# MusicReactiveLEDStrip-V2.net
KiCad netlist of a schematic drawn in EAGLE
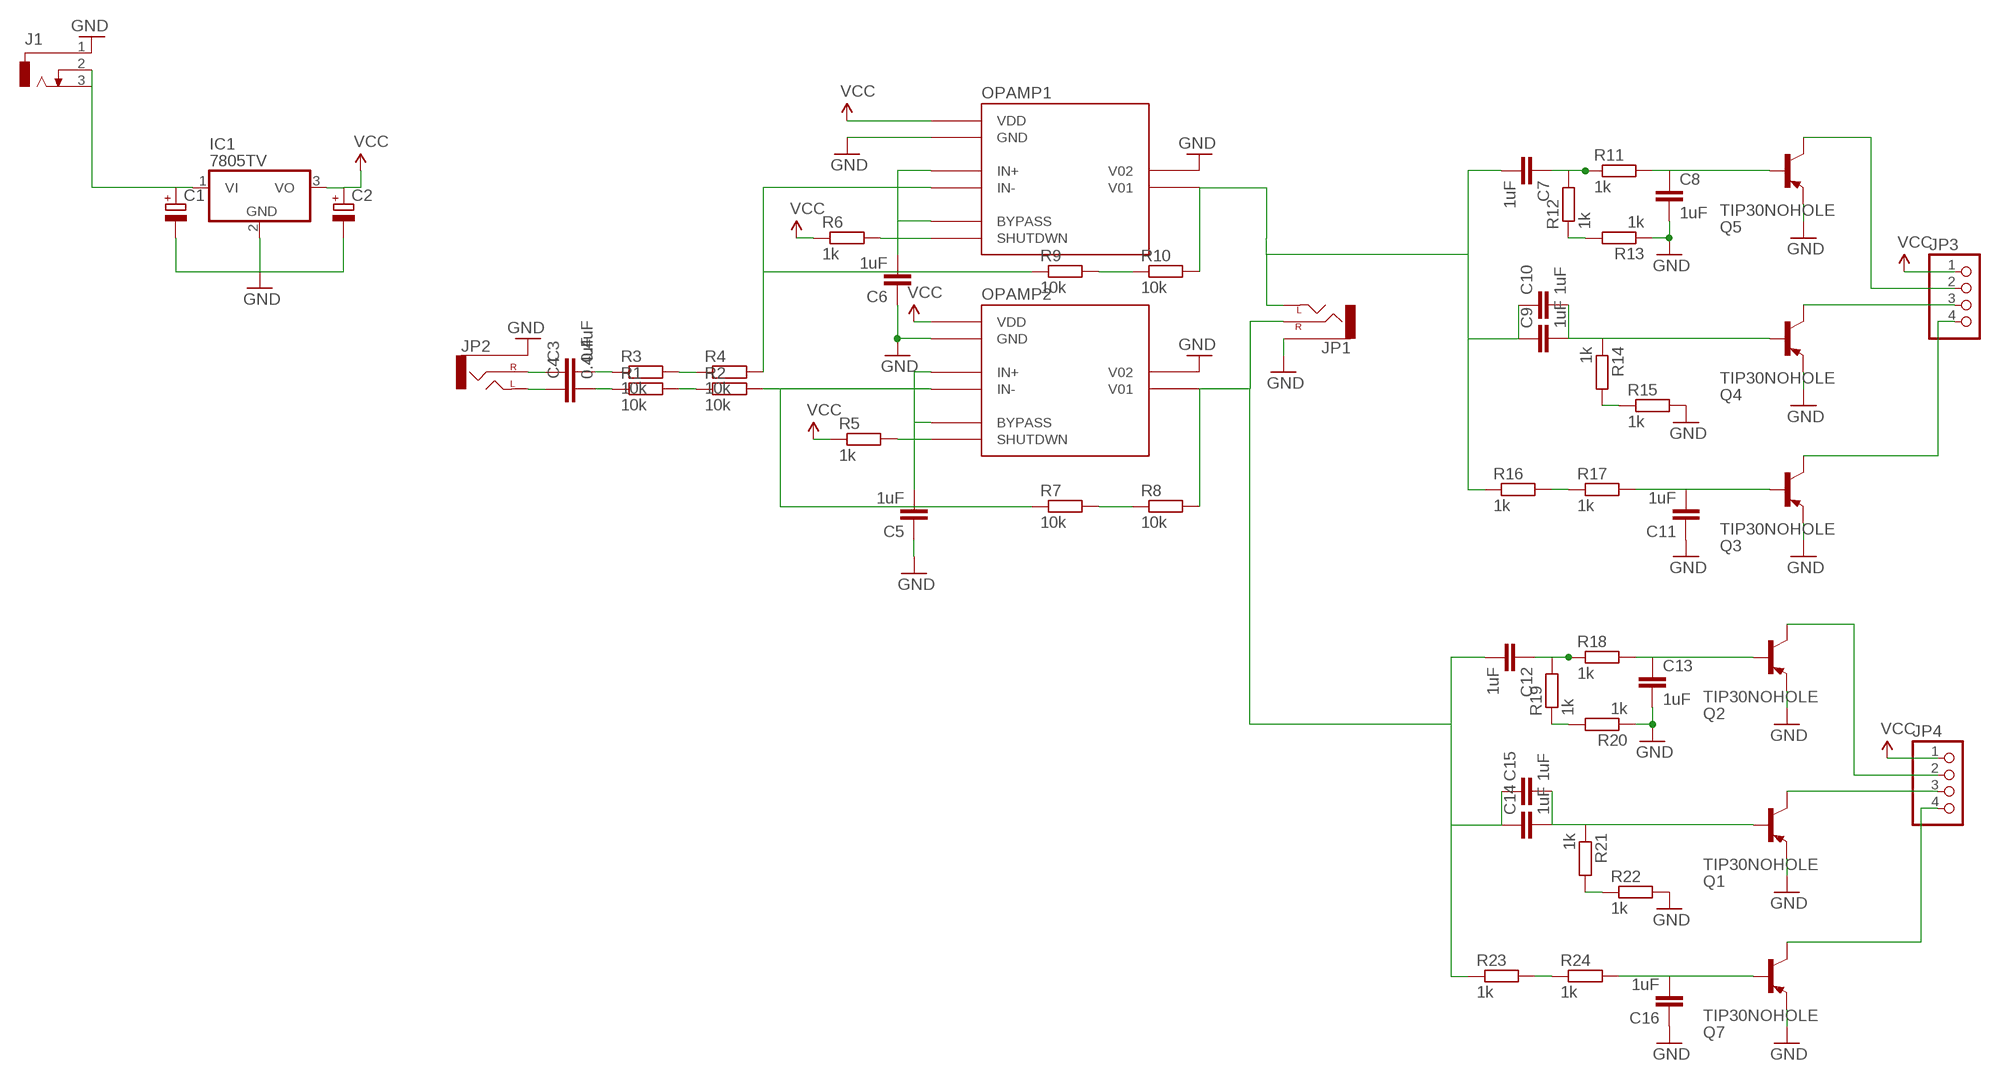
[diagram p0: schematic, sheet 1]

(export (version "E")
  (design (tool "Eeschema 10.0.6"))
  (components
    (comp (ref "C1")
      (value "CPOL-EUE2.5-6")
      (footprint "eagle-import:E2,5-6")
      (libsource (lib "eagle-import") (part "CPOL-EUE2.5-6"))
    )
    (comp (ref "C2")
      (value "CPOL-EUE2.5-6")
      (footprint "eagle-import:E2,5-6")
      (libsource (lib "eagle-import") (part "CPOL-EUE2.5-6"))
    )
    (comp (ref "C3")
      (value "0.4uF")
      (footprint "eagle-import:C050-025X075")
      (libsource (lib "eagle-import") (part "C-EU050-025X075"))
    )
    (comp (ref "C4")
      (value "0.4uF")
      (footprint "eagle-import:C050-025X075")
      (libsource (lib "eagle-import") (part "C-EU050-025X075"))
    )
    (comp (ref "C5")
      (value "1uF")
      (footprint "eagle-import:C050-025X075")
      (libsource (lib "eagle-import") (part "C-EU050-025X075"))
    )
    (comp (ref "C6")
      (value "1uF")
      (footprint "eagle-import:C050-025X075")
      (libsource (lib "eagle-import") (part "C-EU050-025X075"))
    )
    (comp (ref "C7")
      (value "1uF")
      (footprint "eagle-import:C050-025X075")
      (libsource (lib "eagle-import") (part "C-EU050-025X075"))
    )
    (comp (ref "C8")
      (value "1uF")
      (footprint "eagle-import:C050-025X075")
      (libsource (lib "eagle-import") (part "C-EU050-025X075"))
    )
    (comp (ref "C9")
      (value "1uF")
      (footprint "eagle-import:C050-025X075")
      (libsource (lib "eagle-import") (part "C-EU050-025X075"))
    )
    (comp (ref "C10")
      (value "1uF")
      (footprint "eagle-import:C050-025X075")
      (libsource (lib "eagle-import") (part "C-EU050-025X075"))
    )
    (comp (ref "C11")
      (value "1uF")
      (footprint "eagle-import:C050-025X075")
      (libsource (lib "eagle-import") (part "C-EU050-025X075"))
    )
    (comp (ref "C12")
      (value "1uF")
      (footprint "eagle-import:C050-025X075")
      (libsource (lib "eagle-import") (part "C-EU050-025X075"))
    )
    (comp (ref "C13")
      (value "1uF")
      (footprint "eagle-import:C050-025X075")
      (libsource (lib "eagle-import") (part "C-EU050-025X075"))
    )
    (comp (ref "C14")
      (value "1uF")
      (footprint "eagle-import:C050-025X075")
      (libsource (lib "eagle-import") (part "C-EU050-025X075"))
    )
    (comp (ref "C15")
      (value "1uF")
      (footprint "eagle-import:C050-025X075")
      (libsource (lib "eagle-import") (part "C-EU050-025X075"))
    )
    (comp (ref "C16")
      (value "1uF")
      (footprint "eagle-import:C050-025X075")
      (libsource (lib "eagle-import") (part "C-EU050-025X075"))
    )
    (comp (ref "IC1")
      (value "7805TV")
      (footprint "eagle-import:TO220V")
      (libsource (lib "eagle-import") (part "78TV05"))
    )
    (comp (ref "J1")
      (value "DCJ0303")
      (footprint "eagle-import:DCJ0303")
      (libsource (lib "eagle-import") (part "DCJ0303"))
    )
    (comp (ref "JP1")
      (value "AUDIO-JACKPTH")
      (footprint "eagle-import:AUDIO-JACK")
      (libsource (lib "eagle-import") (part "AUDIO-JACKPTH"))
    )
    (comp (ref "JP2")
      (value "AUDIO-JACKPTH")
      (footprint "eagle-import:AUDIO-JACK")
      (libsource (lib "eagle-import") (part "AUDIO-JACKPTH"))
    )
    (comp (ref "JP3")
      (value "PINHD-1X4")
      (footprint "eagle-import:1X04")
      (libsource (lib "eagle-import") (part "PINHD-1X4"))
    )
    (comp (ref "JP4")
      (value "PINHD-1X4")
      (footprint "eagle-import:1X04")
      (libsource (lib "eagle-import") (part "PINHD-1X4"))
    )
    (comp (ref "OPAMP1")
      (value "LM4871")
      (footprint "eagle-import:SO08")
      (libsource (lib "eagle-import") (part "LM4871"))
    )
    (comp (ref "OPAMP2")
      (value "LM4871")
      (footprint "eagle-import:SO08")
      (libsource (lib "eagle-import") (part "LM4871"))
    )
    (comp (ref "Q1")
      (value "TIP30NOHOLE")
      (footprint "eagle-import:TO220-NOHOLE")
      (libsource (lib "eagle-import") (part "TIP30NOHOLE"))
    )
    (comp (ref "Q2")
      (value "TIP30NOHOLE")
      (footprint "eagle-import:TO220-NOHOLE")
      (libsource (lib "eagle-import") (part "TIP30NOHOLE"))
    )
    (comp (ref "Q3")
      (value "TIP30NOHOLE")
      (footprint "eagle-import:TO220-NOHOLE")
      (libsource (lib "eagle-import") (part "TIP30NOHOLE"))
    )
    (comp (ref "Q4")
      (value "TIP30NOHOLE")
      (footprint "eagle-import:TO220-NOHOLE")
      (libsource (lib "eagle-import") (part "TIP30NOHOLE"))
    )
    (comp (ref "Q5")
      (value "TIP30NOHOLE")
      (footprint "eagle-import:TO220-NOHOLE")
      (libsource (lib "eagle-import") (part "TIP30NOHOLE"))
    )
    (comp (ref "Q7")
      (value "TIP30NOHOLE")
      (footprint "eagle-import:TO220-NOHOLE")
      (libsource (lib "eagle-import") (part "TIP30NOHOLE"))
    )
    (comp (ref "R1")
      (value "10k")
      (footprint "eagle-import:0207_10")
      (libsource (lib "eagle-import") (part "R-EU_0207/10"))
    )
    (comp (ref "R2")
      (value "10k")
      (footprint "eagle-import:0207_10")
      (libsource (lib "eagle-import") (part "R-EU_0207/10"))
    )
    (comp (ref "R3")
      (value "10k")
      (footprint "eagle-import:0207_10")
      (libsource (lib "eagle-import") (part "R-EU_0207/10"))
    )
    (comp (ref "R4")
      (value "10k")
      (footprint "eagle-import:0207_10")
      (libsource (lib "eagle-import") (part "R-EU_0207/10"))
    )
    (comp (ref "R5")
      (value "1k")
      (footprint "eagle-import:0207_10")
      (libsource (lib "eagle-import") (part "R-EU_0207/10"))
    )
    (comp (ref "R6")
      (value "1k")
      (footprint "eagle-import:0207_10")
      (libsource (lib "eagle-import") (part "R-EU_0207/10"))
    )
    (comp (ref "R7")
      (value "10k")
      (footprint "eagle-import:0207_10")
      (libsource (lib "eagle-import") (part "R-EU_0207/10"))
    )
    (comp (ref "R8")
      (value "10k")
      (footprint "eagle-import:0207_10")
      (libsource (lib "eagle-import") (part "R-EU_0207/10"))
    )
    (comp (ref "R9")
      (value "10k")
      (footprint "eagle-import:0207_10")
      (libsource (lib "eagle-import") (part "R-EU_0207/10"))
    )
    (comp (ref "R10")
      (value "10k")
      (footprint "eagle-import:0207_10")
      (libsource (lib "eagle-import") (part "R-EU_0207/10"))
    )
    (comp (ref "R11")
      (value "1k")
      (footprint "eagle-import:0207_10")
      (libsource (lib "eagle-import") (part "R-EU_0207/10"))
    )
    (comp (ref "R12")
      (value "1k")
      (footprint "eagle-import:0207_10")
      (libsource (lib "eagle-import") (part "R-EU_0207/10"))
    )
    (comp (ref "R13")
      (value "1k")
      (footprint "eagle-import:0207_10")
      (libsource (lib "eagle-import") (part "R-EU_0207/10"))
    )
    (comp (ref "R14")
      (value "1k")
      (footprint "eagle-import:0207_10")
      (libsource (lib "eagle-import") (part "R-EU_0207/10"))
    )
    (comp (ref "R15")
      (value "1k")
      (footprint "eagle-import:0207_10")
      (libsource (lib "eagle-import") (part "R-EU_0207/10"))
    )
    (comp (ref "R16")
      (value "1k")
      (footprint "eagle-import:0207_10")
      (libsource (lib "eagle-import") (part "R-EU_0207/10"))
    )
    (comp (ref "R17")
      (value "1k")
      (footprint "eagle-import:0207_10")
      (libsource (lib "eagle-import") (part "R-EU_0207/10"))
    )
    (comp (ref "R18")
      (value "1k")
      (footprint "eagle-import:0207_10")
      (libsource (lib "eagle-import") (part "R-EU_0207/10"))
    )
    (comp (ref "R19")
      (value "1k")
      (footprint "eagle-import:0207_10")
      (libsource (lib "eagle-import") (part "R-EU_0207/10"))
    )
    (comp (ref "R20")
      (value "1k")
      (footprint "eagle-import:0207_10")
      (libsource (lib "eagle-import") (part "R-EU_0207/10"))
    )
    (comp (ref "R21")
      (value "1k")
      (footprint "eagle-import:0207_10")
      (libsource (lib "eagle-import") (part "R-EU_0207/10"))
    )
    (comp (ref "R22")
      (value "1k")
      (footprint "eagle-import:0207_10")
      (libsource (lib "eagle-import") (part "R-EU_0207/10"))
    )
    (comp (ref "R23")
      (value "1k")
      (footprint "eagle-import:0207_10")
      (libsource (lib "eagle-import") (part "R-EU_0207/10"))
    )
    (comp (ref "R24")
      (value "1k")
      (footprint "eagle-import:0207_10")
      (libsource (lib "eagle-import") (part "R-EU_0207/10"))
    )
  )
  (nets
    (net (code "1") (name "GND") (class "Default")
      (node (ref "C1") (pin "-") (pinfunction "-_-") (pintype "passive"))
      (node (ref "C11") (pin "1") (pinfunction "1_1") (pintype "passive"))
      (node (ref "C13") (pin "2") (pinfunction "2_2") (pintype "passive"))
      (node (ref "C16") (pin "1") (pinfunction "1_1") (pintype "passive"))
      (node (ref "C2") (pin "-") (pinfunction "-_-") (pintype "passive"))
      (node (ref "C5") (pin "1") (pinfunction "1_1") (pintype "passive"))
      (node (ref "C6") (pin "1") (pinfunction "1_1") (pintype "passive"))
      (node (ref "C8") (pin "2") (pinfunction "2_2") (pintype "passive"))
      (node (ref "IC1") (pin "2") (pinfunction "GND_2") (pintype "passive"))
      (node (ref "J1") (pin "1") (pinfunction "1_1") (pintype "passive"))
      (node (ref "JP1") (pin "SLEEVE") (pinfunction "SLEEVE_SLEEVE") (pintype "bidirectional"))
      (node (ref "JP2") (pin "SLEEVE") (pinfunction "SLEEVE_SLEEVE") (pintype "bidirectional"))
      (node (ref "OPAMP1") (pin "7") (pinfunction "GND_7") (pintype "bidirectional"))
      (node (ref "OPAMP1") (pin "8") (pinfunction "V02_8") (pintype "bidirectional"))
      (node (ref "OPAMP2") (pin "7") (pinfunction "GND_7") (pintype "bidirectional"))
      (node (ref "OPAMP2") (pin "8") (pinfunction "V02_8") (pintype "bidirectional"))
      (node (ref "Q1") (pin "3") (pinfunction "E_3") (pintype "passive"))
      (node (ref "Q2") (pin "3") (pinfunction "E_3") (pintype "passive"))
      (node (ref "Q3") (pin "3") (pinfunction "E_3") (pintype "passive"))
      (node (ref "Q4") (pin "3") (pinfunction "E_3") (pintype "passive"))
      (node (ref "Q5") (pin "3") (pinfunction "E_3") (pintype "passive"))
      (node (ref "Q7") (pin "3") (pinfunction "E_3") (pintype "passive"))
      (node (ref "R13") (pin "1") (pinfunction "1_1") (pintype "passive"))
      (node (ref "R15") (pin "2") (pinfunction "2_2") (pintype "passive"))
      (node (ref "R20") (pin "1") (pinfunction "1_1") (pintype "passive"))
      (node (ref "R22") (pin "2") (pinfunction "2_2") (pintype "passive"))
    )
    (net (code "2") (name "Net-(C3-Pad2)") (class "Default")
      (node (ref "C3") (pin "2") (pinfunction "2_2") (pintype "passive"))
      (node (ref "R3") (pin "1") (pinfunction "1_1") (pintype "passive"))
    )
    (net (code "3") (name "Net-(C4-Pad2)") (class "Default")
      (node (ref "C4") (pin "2") (pinfunction "2_2") (pintype "passive"))
      (node (ref "R1") (pin "1") (pinfunction "1_1") (pintype "passive"))
    )
    (net (code "4") (name "Net-(C7-Pad1)") (class "Default")
      (node (ref "C7") (pin "1") (pinfunction "1_1") (pintype "passive"))
      (node (ref "R11") (pin "1") (pinfunction "1_1") (pintype "passive"))
      (node (ref "R12") (pin "2") (pinfunction "2_2") (pintype "passive"))
    )
    (net (code "5") (name "Net-(C12-Pad1)") (class "Default")
      (node (ref "C12") (pin "1") (pinfunction "1_1") (pintype "passive"))
      (node (ref "R18") (pin "1") (pinfunction "1_1") (pintype "passive"))
      (node (ref "R19") (pin "2") (pinfunction "2_2") (pintype "passive"))
    )
    (net (code "6") (name "Net-(IC1-VI)") (class "Default")
      (node (ref "C1") (pin "+") (pinfunction "+_+") (pintype "passive"))
      (node (ref "IC1") (pin "1") (pinfunction "VI_1") (pintype "input"))
      (node (ref "J1") (pin "2") (pinfunction "2_2") (pintype "passive"))
      (node (ref "J1") (pin "3") (pinfunction "3_3") (pintype "passive"))
    )
    (net (code "7") (name "Net-(JP1-LEFT)") (class "Default")
      (node (ref "C10") (pin "1") (pinfunction "1_1") (pintype "passive"))
      (node (ref "C7") (pin "2") (pinfunction "2_2") (pintype "passive"))
      (node (ref "C9") (pin "1") (pinfunction "1_1") (pintype "passive"))
      (node (ref "JP1") (pin "TIP") (pinfunction "LEFT_TIP") (pintype "bidirectional"))
      (node (ref "OPAMP1") (pin "5") (pinfunction "V01_5") (pintype "bidirectional"))
      (node (ref "R10") (pin "2") (pinfunction "2_2") (pintype "passive"))
      (node (ref "R16") (pin "1") (pinfunction "1_1") (pintype "passive"))
    )
    (net (code "8") (name "Net-(JP1-RIGHT)") (class "Default")
      (node (ref "C12") (pin "2") (pinfunction "2_2") (pintype "passive"))
      (node (ref "C14") (pin "1") (pinfunction "1_1") (pintype "passive"))
      (node (ref "C15") (pin "1") (pinfunction "1_1") (pintype "passive"))
      (node (ref "JP1") (pin "RING") (pinfunction "RIGHT_RING") (pintype "bidirectional"))
      (node (ref "OPAMP2") (pin "5") (pinfunction "V01_5") (pintype "bidirectional"))
      (node (ref "R23") (pin "1") (pinfunction "1_1") (pintype "passive"))
      (node (ref "R8") (pin "2") (pinfunction "2_2") (pintype "passive"))
    )
    (net (code "9") (name "Net-(JP2-LEFT)") (class "Default")
      (node (ref "C4") (pin "1") (pinfunction "1_1") (pintype "passive"))
      (node (ref "JP2") (pin "TIP") (pinfunction "LEFT_TIP") (pintype "bidirectional"))
    )
    (net (code "10") (name "Net-(JP2-RIGHT)") (class "Default")
      (node (ref "C3") (pin "1") (pinfunction "1_1") (pintype "passive"))
      (node (ref "JP2") (pin "RING") (pinfunction "RIGHT_RING") (pintype "bidirectional"))
    )
    (net (code "11") (name "Net-(OPAMP1-BYPASS)") (class "Default")
      (node (ref "C6") (pin "2") (pinfunction "2_2") (pintype "passive"))
      (node (ref "OPAMP1") (pin "2") (pinfunction "BYPASS_2") (pintype "bidirectional"))
      (node (ref "OPAMP1") (pin "3") (pinfunction "IN+_3") (pintype "bidirectional"))
    )
    (net (code "12") (name "Net-(OPAMP1-IN-)") (class "Default")
      (node (ref "OPAMP1") (pin "4") (pinfunction "IN-_4") (pintype "bidirectional"))
      (node (ref "R4") (pin "2") (pinfunction "2_2") (pintype "passive"))
      (node (ref "R9") (pin "1") (pinfunction "1_1") (pintype "passive"))
    )
    (net (code "13") (name "Net-(OPAMP1-SHUTDWN)") (class "Default")
      (node (ref "OPAMP1") (pin "1") (pinfunction "SHUTDWN_1") (pintype "bidirectional"))
      (node (ref "R6") (pin "2") (pinfunction "2_2") (pintype "passive"))
    )
    (net (code "14") (name "Net-(OPAMP2-BYPASS)") (class "Default")
      (node (ref "C5") (pin "2") (pinfunction "2_2") (pintype "passive"))
      (node (ref "OPAMP2") (pin "2") (pinfunction "BYPASS_2") (pintype "bidirectional"))
      (node (ref "OPAMP2") (pin "3") (pinfunction "IN+_3") (pintype "bidirectional"))
    )
    (net (code "15") (name "Net-(OPAMP2-IN-)") (class "Default")
      (node (ref "OPAMP2") (pin "4") (pinfunction "IN-_4") (pintype "bidirectional"))
      (node (ref "R2") (pin "2") (pinfunction "2_2") (pintype "passive"))
      (node (ref "R7") (pin "1") (pinfunction "1_1") (pintype "passive"))
    )
    (net (code "16") (name "Net-(OPAMP2-SHUTDWN)") (class "Default")
      (node (ref "OPAMP2") (pin "1") (pinfunction "SHUTDWN_1") (pintype "bidirectional"))
      (node (ref "R5") (pin "2") (pinfunction "2_2") (pintype "passive"))
    )
    (net (code "17") (name "Net-(Q1-B)") (class "Default")
      (node (ref "C14") (pin "2") (pinfunction "2_2") (pintype "passive"))
      (node (ref "C15") (pin "2") (pinfunction "2_2") (pintype "passive"))
      (node (ref "Q1") (pin "1") (pinfunction "B_1") (pintype "passive"))
      (node (ref "R21") (pin "1") (pinfunction "1_1") (pintype "passive"))
    )
    (net (code "18") (name "Net-(Q1-C)") (class "Default")
      (node (ref "JP4") (pin "3") (pinfunction "3_3") (pintype "passive"))
      (node (ref "Q1") (pin "2") (pinfunction "C_2") (pintype "passive"))
    )
    (net (code "19") (name "Net-(Q2-B)") (class "Default")
      (node (ref "C13") (pin "1") (pinfunction "1_1") (pintype "passive"))
      (node (ref "Q2") (pin "1") (pinfunction "B_1") (pintype "passive"))
      (node (ref "R18") (pin "2") (pinfunction "2_2") (pintype "passive"))
    )
    (net (code "20") (name "Net-(Q2-C)") (class "Default")
      (node (ref "JP4") (pin "2") (pinfunction "2_2") (pintype "passive"))
      (node (ref "Q2") (pin "2") (pinfunction "C_2") (pintype "passive"))
    )
    (net (code "21") (name "Net-(Q3-B)") (class "Default")
      (node (ref "C11") (pin "2") (pinfunction "2_2") (pintype "passive"))
      (node (ref "Q3") (pin "1") (pinfunction "B_1") (pintype "passive"))
      (node (ref "R17") (pin "2") (pinfunction "2_2") (pintype "passive"))
    )
    (net (code "22") (name "Net-(Q3-C)") (class "Default")
      (node (ref "JP3") (pin "4") (pinfunction "4_4") (pintype "passive"))
      (node (ref "Q3") (pin "2") (pinfunction "C_2") (pintype "passive"))
    )
    (net (code "23") (name "Net-(Q4-B)") (class "Default")
      (node (ref "C10") (pin "2") (pinfunction "2_2") (pintype "passive"))
      (node (ref "C9") (pin "2") (pinfunction "2_2") (pintype "passive"))
      (node (ref "Q4") (pin "1") (pinfunction "B_1") (pintype "passive"))
      (node (ref "R14") (pin "1") (pinfunction "1_1") (pintype "passive"))
    )
    (net (code "24") (name "Net-(Q4-C)") (class "Default")
      (node (ref "JP3") (pin "3") (pinfunction "3_3") (pintype "passive"))
      (node (ref "Q4") (pin "2") (pinfunction "C_2") (pintype "passive"))
    )
    (net (code "25") (name "Net-(Q5-B)") (class "Default")
      (node (ref "C8") (pin "1") (pinfunction "1_1") (pintype "passive"))
      (node (ref "Q5") (pin "1") (pinfunction "B_1") (pintype "passive"))
      (node (ref "R11") (pin "2") (pinfunction "2_2") (pintype "passive"))
    )
    (net (code "26") (name "Net-(Q5-C)") (class "Default")
      (node (ref "JP3") (pin "2") (pinfunction "2_2") (pintype "passive"))
      (node (ref "Q5") (pin "2") (pinfunction "C_2") (pintype "passive"))
    )
    (net (code "27") (name "Net-(Q7-B)") (class "Default")
      (node (ref "C16") (pin "2") (pinfunction "2_2") (pintype "passive"))
      (node (ref "Q7") (pin "1") (pinfunction "B_1") (pintype "passive"))
      (node (ref "R24") (pin "2") (pinfunction "2_2") (pintype "passive"))
    )
    (net (code "28") (name "Net-(Q7-C)") (class "Default")
      (node (ref "JP4") (pin "4") (pinfunction "4_4") (pintype "passive"))
      (node (ref "Q7") (pin "2") (pinfunction "C_2") (pintype "passive"))
    )
    (net (code "29") (name "Net-(R1-Pad2)") (class "Default")
      (node (ref "R1") (pin "2") (pinfunction "2_2") (pintype "passive"))
      (node (ref "R2") (pin "1") (pinfunction "1_1") (pintype "passive"))
    )
    (net (code "30") (name "Net-(R3-Pad2)") (class "Default")
      (node (ref "R3") (pin "2") (pinfunction "2_2") (pintype "passive"))
      (node (ref "R4") (pin "1") (pinfunction "1_1") (pintype "passive"))
    )
    (net (code "31") (name "Net-(R7-Pad2)") (class "Default")
      (node (ref "R7") (pin "2") (pinfunction "2_2") (pintype "passive"))
      (node (ref "R8") (pin "1") (pinfunction "1_1") (pintype "passive"))
    )
    (net (code "32") (name "Net-(R10-Pad1)") (class "Default")
      (node (ref "R10") (pin "1") (pinfunction "1_1") (pintype "passive"))
      (node (ref "R9") (pin "2") (pinfunction "2_2") (pintype "passive"))
    )
    (net (code "33") (name "Net-(R12-Pad1)") (class "Default")
      (node (ref "R12") (pin "1") (pinfunction "1_1") (pintype "passive"))
      (node (ref "R13") (pin "2") (pinfunction "2_2") (pintype "passive"))
    )
    (net (code "34") (name "Net-(R14-Pad2)") (class "Default")
      (node (ref "R14") (pin "2") (pinfunction "2_2") (pintype "passive"))
      (node (ref "R15") (pin "1") (pinfunction "1_1") (pintype "passive"))
    )
    (net (code "35") (name "Net-(R16-Pad2)") (class "Default")
      (node (ref "R16") (pin "2") (pinfunction "2_2") (pintype "passive"))
      (node (ref "R17") (pin "1") (pinfunction "1_1") (pintype "passive"))
    )
    (net (code "36") (name "Net-(R19-Pad1)") (class "Default")
      (node (ref "R19") (pin "1") (pinfunction "1_1") (pintype "passive"))
      (node (ref "R20") (pin "2") (pinfunction "2_2") (pintype "passive"))
    )
    (net (code "37") (name "Net-(R21-Pad2)") (class "Default")
      (node (ref "R21") (pin "2") (pinfunction "2_2") (pintype "passive"))
      (node (ref "R22") (pin "1") (pinfunction "1_1") (pintype "passive"))
    )
    (net (code "38") (name "Net-(R23-Pad2)") (class "Default")
      (node (ref "R23") (pin "2") (pinfunction "2_2") (pintype "passive"))
      (node (ref "R24") (pin "1") (pinfunction "1_1") (pintype "passive"))
    )
    (net (code "39") (name "VCC") (class "Default")
      (node (ref "C2") (pin "+") (pinfunction "+_+") (pintype "passive"))
      (node (ref "IC1") (pin "3") (pinfunction "VO_3") (pintype "passive"))
      (node (ref "JP3") (pin "1") (pinfunction "1_1") (pintype "passive"))
      (node (ref "JP4") (pin "1") (pinfunction "1_1") (pintype "passive"))
      (node (ref "OPAMP1") (pin "6") (pinfunction "VDD_6") (pintype "bidirectional"))
      (node (ref "OPAMP2") (pin "6") (pinfunction "VDD_6") (pintype "bidirectional"))
      (node (ref "R5") (pin "1") (pinfunction "1_1") (pintype "passive"))
      (node (ref "R6") (pin "1") (pinfunction "1_1") (pintype "passive"))
    )
  )
)
